# 4x4-soundboard.net
KiCad netlist of a schematic drawn in EAGLE
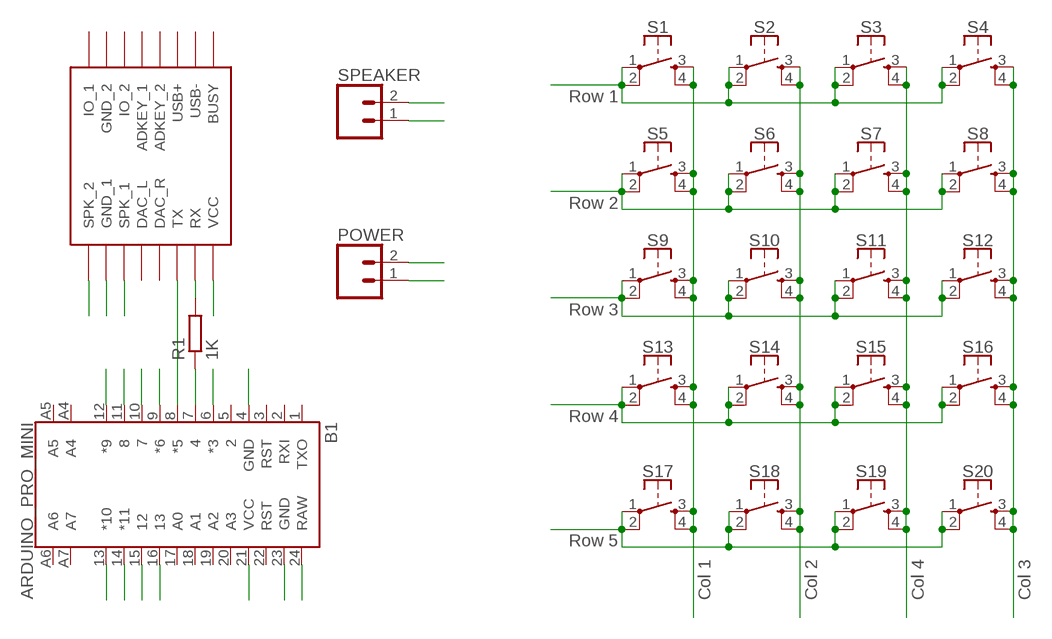
[diagram p0: schematic, sheet 1]

(export (version "E")
  (design (tool "Eeschema 10.0.6"))
  (components
    (comp (ref "B1")
      (value "ARDUINO_PRO_MINI")
      (footprint "eagle-import:ARDUINO_PRO_MINI")
      (libsource (lib "eagle-import") (part "ARDUINO_PRO_MINI"))
    )
    (comp (ref "POWER")
      (value "CONN_02")
      (footprint "eagle-import:1X02")
      (libsource (lib "eagle-import") (part "CONN_02"))
    )
    (comp (ref "R1")
      (value "1K")
      (footprint "eagle-import:0207_10")
      (libsource (lib "eagle-import") (part "R-EU_0207/10"))
    )
    (comp (ref "S1")
      (value "MOMENTARY-SWITCH-SPST-2-SMD-5.2MM")
      (footprint "eagle-import:TACTILE_SWITCH_SMD_5.2MM")
      (libsource (lib "eagle-import") (part "MOMENTARY-SWITCH-SPST-2-SMD-5.2MM"))
    )
    (comp (ref "S2")
      (value "MOMENTARY-SWITCH-SPST-2-SMD-5.2MM")
      (footprint "eagle-import:TACTILE_SWITCH_SMD_5.2MM")
      (libsource (lib "eagle-import") (part "MOMENTARY-SWITCH-SPST-2-SMD-5.2MM"))
    )
    (comp (ref "S3")
      (value "MOMENTARY-SWITCH-SPST-2-SMD-5.2MM")
      (footprint "eagle-import:TACTILE_SWITCH_SMD_5.2MM")
      (libsource (lib "eagle-import") (part "MOMENTARY-SWITCH-SPST-2-SMD-5.2MM"))
    )
    (comp (ref "S4")
      (value "MOMENTARY-SWITCH-SPST-2-SMD-5.2MM")
      (footprint "eagle-import:TACTILE_SWITCH_SMD_5.2MM")
      (libsource (lib "eagle-import") (part "MOMENTARY-SWITCH-SPST-2-SMD-5.2MM"))
    )
    (comp (ref "S5")
      (value "MOMENTARY-SWITCH-SPST-2-SMD-5.2MM")
      (footprint "eagle-import:TACTILE_SWITCH_SMD_5.2MM")
      (libsource (lib "eagle-import") (part "MOMENTARY-SWITCH-SPST-2-SMD-5.2MM"))
    )
    (comp (ref "S6")
      (value "MOMENTARY-SWITCH-SPST-2-SMD-5.2MM")
      (footprint "eagle-import:TACTILE_SWITCH_SMD_5.2MM")
      (libsource (lib "eagle-import") (part "MOMENTARY-SWITCH-SPST-2-SMD-5.2MM"))
    )
    (comp (ref "S7")
      (value "MOMENTARY-SWITCH-SPST-2-SMD-5.2MM")
      (footprint "eagle-import:TACTILE_SWITCH_SMD_5.2MM")
      (libsource (lib "eagle-import") (part "MOMENTARY-SWITCH-SPST-2-SMD-5.2MM"))
    )
    (comp (ref "S8")
      (value "MOMENTARY-SWITCH-SPST-2-SMD-5.2MM")
      (footprint "eagle-import:TACTILE_SWITCH_SMD_5.2MM")
      (libsource (lib "eagle-import") (part "MOMENTARY-SWITCH-SPST-2-SMD-5.2MM"))
    )
    (comp (ref "S9")
      (value "MOMENTARY-SWITCH-SPST-2-SMD-5.2MM")
      (footprint "eagle-import:TACTILE_SWITCH_SMD_5.2MM")
      (libsource (lib "eagle-import") (part "MOMENTARY-SWITCH-SPST-2-SMD-5.2MM"))
    )
    (comp (ref "S10")
      (value "MOMENTARY-SWITCH-SPST-2-SMD-5.2MM")
      (footprint "eagle-import:TACTILE_SWITCH_SMD_5.2MM")
      (libsource (lib "eagle-import") (part "MOMENTARY-SWITCH-SPST-2-SMD-5.2MM"))
    )
    (comp (ref "S11")
      (value "MOMENTARY-SWITCH-SPST-2-SMD-5.2MM")
      (footprint "eagle-import:TACTILE_SWITCH_SMD_5.2MM")
      (libsource (lib "eagle-import") (part "MOMENTARY-SWITCH-SPST-2-SMD-5.2MM"))
    )
    (comp (ref "S12")
      (value "MOMENTARY-SWITCH-SPST-2-SMD-5.2MM")
      (footprint "eagle-import:TACTILE_SWITCH_SMD_5.2MM")
      (libsource (lib "eagle-import") (part "MOMENTARY-SWITCH-SPST-2-SMD-5.2MM"))
    )
    (comp (ref "S13")
      (value "MOMENTARY-SWITCH-SPST-2-SMD-5.2MM")
      (footprint "eagle-import:TACTILE_SWITCH_SMD_5.2MM")
      (libsource (lib "eagle-import") (part "MOMENTARY-SWITCH-SPST-2-SMD-5.2MM"))
    )
    (comp (ref "S14")
      (value "MOMENTARY-SWITCH-SPST-2-SMD-5.2MM")
      (footprint "eagle-import:TACTILE_SWITCH_SMD_5.2MM")
      (libsource (lib "eagle-import") (part "MOMENTARY-SWITCH-SPST-2-SMD-5.2MM"))
    )
    (comp (ref "S15")
      (value "MOMENTARY-SWITCH-SPST-2-SMD-5.2MM")
      (footprint "eagle-import:TACTILE_SWITCH_SMD_5.2MM")
      (libsource (lib "eagle-import") (part "MOMENTARY-SWITCH-SPST-2-SMD-5.2MM"))
    )
    (comp (ref "S16")
      (value "MOMENTARY-SWITCH-SPST-2-SMD-5.2MM")
      (footprint "eagle-import:TACTILE_SWITCH_SMD_5.2MM")
      (libsource (lib "eagle-import") (part "MOMENTARY-SWITCH-SPST-2-SMD-5.2MM"))
    )
    (comp (ref "S17")
      (value "MOMENTARY-SWITCH-SPST-2-SMD-5.2MM")
      (footprint "eagle-import:TACTILE_SWITCH_SMD_5.2MM")
      (libsource (lib "eagle-import") (part "MOMENTARY-SWITCH-SPST-2-SMD-5.2MM"))
    )
    (comp (ref "S18")
      (value "MOMENTARY-SWITCH-SPST-2-SMD-5.2MM")
      (footprint "eagle-import:TACTILE_SWITCH_SMD_5.2MM")
      (libsource (lib "eagle-import") (part "MOMENTARY-SWITCH-SPST-2-SMD-5.2MM"))
    )
    (comp (ref "S19")
      (value "MOMENTARY-SWITCH-SPST-2-SMD-5.2MM")
      (footprint "eagle-import:TACTILE_SWITCH_SMD_5.2MM")
      (libsource (lib "eagle-import") (part "MOMENTARY-SWITCH-SPST-2-SMD-5.2MM"))
    )
    (comp (ref "S20")
      (value "MOMENTARY-SWITCH-SPST-2-SMD-5.2MM")
      (footprint "eagle-import:TACTILE_SWITCH_SMD_5.2MM")
      (libsource (lib "eagle-import") (part "MOMENTARY-SWITCH-SPST-2-SMD-5.2MM"))
    )
    (comp (ref "SPEAKER")
      (value "CONN_02")
      (footprint "eagle-import:1X02")
      (libsource (lib "eagle-import") (part "CONN_02"))
    )
    (comp (ref "U$1")
      (value "DFPLAYER")
      (footprint "eagle-import:DFPLAYER")
      (libsource (lib "eagle-import") (part "DFPLAYER"))
    )
  )
  (nets
    (net (code "1") (name "/5V") (class "Default")
      (node (ref "B1") (pin "21") (pinfunction "VCC_21") (pintype "power_in"))
      (node (ref "U$1") (pin "VCC") (pinfunction "VCC_VCC") (pintype "bidirectional"))
    )
    (net (code "2") (name "/COL1") (class "Default")
      (node (ref "B1") (pin "13") (pinfunction "*10_13") (pintype "bidirectional"))
      (node (ref "S1") (pin "3") (pinfunction "3_3") (pintype "passive"))
      (node (ref "S1") (pin "4") (pinfunction "4_4") (pintype "passive"))
      (node (ref "S13") (pin "3") (pinfunction "3_3") (pintype "passive"))
      (node (ref "S13") (pin "4") (pinfunction "4_4") (pintype "passive"))
      (node (ref "S17") (pin "3") (pinfunction "3_3") (pintype "passive"))
      (node (ref "S17") (pin "4") (pinfunction "4_4") (pintype "passive"))
      (node (ref "S5") (pin "3") (pinfunction "3_3") (pintype "passive"))
      (node (ref "S5") (pin "4") (pinfunction "4_4") (pintype "passive"))
      (node (ref "S9") (pin "3") (pinfunction "3_3") (pintype "passive"))
      (node (ref "S9") (pin "4") (pinfunction "4_4") (pintype "passive"))
    )
    (net (code "3") (name "/COL2") (class "Default")
      (node (ref "B1") (pin "14") (pinfunction "*11_14") (pintype "bidirectional"))
      (node (ref "S10") (pin "3") (pinfunction "3_3") (pintype "passive"))
      (node (ref "S10") (pin "4") (pinfunction "4_4") (pintype "passive"))
      (node (ref "S14") (pin "3") (pinfunction "3_3") (pintype "passive"))
      (node (ref "S14") (pin "4") (pinfunction "4_4") (pintype "passive"))
      (node (ref "S18") (pin "3") (pinfunction "3_3") (pintype "passive"))
      (node (ref "S18") (pin "4") (pinfunction "4_4") (pintype "passive"))
      (node (ref "S2") (pin "3") (pinfunction "3_3") (pintype "passive"))
      (node (ref "S2") (pin "4") (pinfunction "4_4") (pintype "passive"))
      (node (ref "S6") (pin "3") (pinfunction "3_3") (pintype "passive"))
      (node (ref "S6") (pin "4") (pinfunction "4_4") (pintype "passive"))
    )
    (net (code "4") (name "/COL3") (class "Default")
      (node (ref "B1") (pin "15") (pinfunction "12_15") (pintype "bidirectional"))
      (node (ref "S11") (pin "3") (pinfunction "3_3") (pintype "passive"))
      (node (ref "S11") (pin "4") (pinfunction "4_4") (pintype "passive"))
      (node (ref "S15") (pin "3") (pinfunction "3_3") (pintype "passive"))
      (node (ref "S15") (pin "4") (pinfunction "4_4") (pintype "passive"))
      (node (ref "S19") (pin "3") (pinfunction "3_3") (pintype "passive"))
      (node (ref "S19") (pin "4") (pinfunction "4_4") (pintype "passive"))
      (node (ref "S3") (pin "3") (pinfunction "3_3") (pintype "passive"))
      (node (ref "S3") (pin "4") (pinfunction "4_4") (pintype "passive"))
      (node (ref "S7") (pin "3") (pinfunction "3_3") (pintype "passive"))
      (node (ref "S7") (pin "4") (pinfunction "4_4") (pintype "passive"))
    )
    (net (code "5") (name "/COL4") (class "Default")
      (node (ref "B1") (pin "16") (pinfunction "13_16") (pintype "bidirectional"))
      (node (ref "S12") (pin "3") (pinfunction "3_3") (pintype "passive"))
      (node (ref "S12") (pin "4") (pinfunction "4_4") (pintype "passive"))
      (node (ref "S16") (pin "3") (pinfunction "3_3") (pintype "passive"))
      (node (ref "S16") (pin "4") (pinfunction "4_4") (pintype "passive"))
      (node (ref "S20") (pin "3") (pinfunction "3_3") (pintype "passive"))
      (node (ref "S20") (pin "4") (pinfunction "4_4") (pintype "passive"))
      (node (ref "S4") (pin "3") (pinfunction "3_3") (pintype "passive"))
      (node (ref "S4") (pin "4") (pinfunction "4_4") (pintype "passive"))
      (node (ref "S8") (pin "3") (pinfunction "3_3") (pintype "passive"))
      (node (ref "S8") (pin "4") (pinfunction "4_4") (pintype "passive"))
    )
    (net (code "6") (name "/GND") (class "Default")
      (node (ref "B1") (pin "23") (pinfunction "GND_23") (pintype "power_in"))
      (node (ref "B1") (pin "4") (pinfunction "GND_4") (pintype "power_in"))
      (node (ref "POWER") (pin "2") (pinfunction "2_2") (pintype "passive"))
      (node (ref "U$1") (pin "GND_1") (pinfunction "GND_1_GND_1") (pintype "bidirectional"))
    )
    (net (code "7") (name "/ROW2") (class "Default")
      (node (ref "B1") (pin "9") (pinfunction "*6_9") (pintype "bidirectional"))
      (node (ref "S5") (pin "1") (pinfunction "1_1") (pintype "passive"))
      (node (ref "S5") (pin "2") (pinfunction "2_2") (pintype "passive"))
      (node (ref "S6") (pin "1") (pinfunction "1_1") (pintype "passive"))
      (node (ref "S6") (pin "2") (pinfunction "2_2") (pintype "passive"))
      (node (ref "S7") (pin "1") (pinfunction "1_1") (pintype "passive"))
      (node (ref "S7") (pin "2") (pinfunction "2_2") (pintype "passive"))
      (node (ref "S8") (pin "1") (pinfunction "1_1") (pintype "passive"))
      (node (ref "S8") (pin "2") (pinfunction "2_2") (pintype "passive"))
    )
    (net (code "8") (name "/ROW3") (class "Default")
      (node (ref "B1") (pin "10") (pinfunction "7_10") (pintype "bidirectional"))
      (node (ref "S10") (pin "1") (pinfunction "1_1") (pintype "passive"))
      (node (ref "S10") (pin "2") (pinfunction "2_2") (pintype "passive"))
      (node (ref "S11") (pin "1") (pinfunction "1_1") (pintype "passive"))
      (node (ref "S11") (pin "2") (pinfunction "2_2") (pintype "passive"))
      (node (ref "S12") (pin "1") (pinfunction "1_1") (pintype "passive"))
      (node (ref "S12") (pin "2") (pinfunction "2_2") (pintype "passive"))
      (node (ref "S9") (pin "1") (pinfunction "1_1") (pintype "passive"))
      (node (ref "S9") (pin "2") (pinfunction "2_2") (pintype "passive"))
    )
    (net (code "9") (name "/ROW4") (class "Default")
      (node (ref "B1") (pin "11") (pinfunction "8_11") (pintype "bidirectional"))
      (node (ref "S13") (pin "1") (pinfunction "1_1") (pintype "passive"))
      (node (ref "S13") (pin "2") (pinfunction "2_2") (pintype "passive"))
      (node (ref "S14") (pin "1") (pinfunction "1_1") (pintype "passive"))
      (node (ref "S14") (pin "2") (pinfunction "2_2") (pintype "passive"))
      (node (ref "S15") (pin "1") (pinfunction "1_1") (pintype "passive"))
      (node (ref "S15") (pin "2") (pinfunction "2_2") (pintype "passive"))
      (node (ref "S16") (pin "1") (pinfunction "1_1") (pintype "passive"))
      (node (ref "S16") (pin "2") (pinfunction "2_2") (pintype "passive"))
    )
    (net (code "10") (name "/ROW5") (class "Default")
      (node (ref "B1") (pin "12") (pinfunction "*9_12") (pintype "bidirectional"))
      (node (ref "S17") (pin "1") (pinfunction "1_1") (pintype "passive"))
      (node (ref "S17") (pin "2") (pinfunction "2_2") (pintype "passive"))
      (node (ref "S18") (pin "1") (pinfunction "1_1") (pintype "passive"))
      (node (ref "S18") (pin "2") (pinfunction "2_2") (pintype "passive"))
      (node (ref "S19") (pin "1") (pinfunction "1_1") (pintype "passive"))
      (node (ref "S19") (pin "2") (pinfunction "2_2") (pintype "passive"))
      (node (ref "S20") (pin "1") (pinfunction "1_1") (pintype "passive"))
      (node (ref "S20") (pin "2") (pinfunction "2_2") (pintype "passive"))
    )
    (net (code "11") (name "/SPK+") (class "Default")
      (node (ref "SPEAKER") (pin "1") (pinfunction "1_1") (pintype "passive"))
      (node (ref "U$1") (pin "SPK1") (pinfunction "SPK_1_SPK1") (pintype "bidirectional"))
    )
    (net (code "12") (name "/SPK-") (class "Default")
      (node (ref "SPEAKER") (pin "2") (pinfunction "2_2") (pintype "passive"))
      (node (ref "U$1") (pin "SPK2") (pinfunction "SPK_2_SPK2") (pintype "bidirectional"))
    )
    (net (code "13") (name "/SRX") (class "Default")
      (node (ref "B1") (pin "6") (pinfunction "*3_6") (pintype "bidirectional"))
      (node (ref "B1") (pin "8") (pinfunction "*5_8") (pintype "bidirectional"))
      (node (ref "U$1") (pin "TX") (pinfunction "TX_TX") (pintype "bidirectional"))
    )
    (net (code "14") (name "/VIN") (class "Default")
      (node (ref "B1") (pin "24") (pinfunction "RAW_24") (pintype "power_in"))
      (node (ref "POWER") (pin "1") (pinfunction "1_1") (pintype "passive"))
    )
    (net (code "15") (name "Net-(B1-4)") (class "Default")
      (node (ref "B1") (pin "7") (pinfunction "4_7") (pintype "bidirectional"))
      (node (ref "R1") (pin "1") (pinfunction "1_1") (pintype "passive"))
    )
    (net (code "16") (name "Net-(R1-Pad2)") (class "Default")
      (node (ref "R1") (pin "2") (pinfunction "2_2") (pintype "passive"))
      (node (ref "U$1") (pin "RX") (pinfunction "RX_RX") (pintype "bidirectional"))
    )
    (net (code "17") (name "Net-(S1-Pad1)") (class "Default")
      (node (ref "S1") (pin "1") (pinfunction "1_1") (pintype "passive"))
      (node (ref "S1") (pin "2") (pinfunction "2_2") (pintype "passive"))
      (node (ref "S2") (pin "1") (pinfunction "1_1") (pintype "passive"))
      (node (ref "S2") (pin "2") (pinfunction "2_2") (pintype "passive"))
      (node (ref "S3") (pin "1") (pinfunction "1_1") (pintype "passive"))
      (node (ref "S3") (pin "2") (pinfunction "2_2") (pintype "passive"))
      (node (ref "S4") (pin "1") (pinfunction "1_1") (pintype "passive"))
      (node (ref "S4") (pin "2") (pinfunction "2_2") (pintype "passive"))
    )
    (net (code "18") (name "unconnected-(B1-2-Pad5)") (class "Default")
      (node (ref "B1") (pin "5") (pinfunction "2_5") (pintype "bidirectional"))
    )
    (net (code "19") (name "unconnected-(B1-A0-Pad17)") (class "Default")
      (node (ref "B1") (pin "17") (pinfunction "A0_17") (pintype "bidirectional"))
    )
    (net (code "20") (name "unconnected-(B1-A1-Pad18)") (class "Default")
      (node (ref "B1") (pin "18") (pinfunction "A1_18") (pintype "bidirectional"))
    )
    (net (code "21") (name "unconnected-(B1-A2-Pad19)") (class "Default")
      (node (ref "B1") (pin "19") (pinfunction "A2_19") (pintype "bidirectional"))
    )
    (net (code "22") (name "unconnected-(B1-A3-Pad20)") (class "Default")
      (node (ref "B1") (pin "20") (pinfunction "A3_20") (pintype "bidirectional"))
    )
    (net (code "23") (name "unconnected-(B1-PadA4)") (class "Default")
      (node (ref "B1") (pin "A4") (pinfunction "A4_A4") (pintype "bidirectional"))
    )
    (net (code "24") (name "unconnected-(B1-PadA5)") (class "Default")
      (node (ref "B1") (pin "A5") (pinfunction "A5_A5") (pintype "bidirectional"))
    )
    (net (code "25") (name "unconnected-(B1-PadA6)") (class "Default")
      (node (ref "B1") (pin "A6") (pinfunction "A6_A6") (pintype "bidirectional"))
    )
    (net (code "26") (name "unconnected-(B1-PadA7)") (class "Default")
      (node (ref "B1") (pin "A7") (pinfunction "A7_A7") (pintype "bidirectional"))
    )
    (net (code "27") (name "unconnected-(B1-RST-Pad3)") (class "Default")
      (node (ref "B1") (pin "3") (pinfunction "RST_3") (pintype "bidirectional"))
    )
    (net (code "28") (name "unconnected-(B1-RST-Pad22)") (class "Default")
      (node (ref "B1") (pin "22") (pinfunction "RST_22") (pintype "bidirectional"))
    )
    (net (code "29") (name "unconnected-(B1-RXI-Pad2)") (class "Default")
      (node (ref "B1") (pin "2") (pinfunction "RXI_2") (pintype "bidirectional"))
    )
    (net (code "30") (name "unconnected-(B1-TXO-Pad1)") (class "Default")
      (node (ref "B1") (pin "1") (pinfunction "TXO_1") (pintype "bidirectional"))
    )
    (net (code "31") (name "unconnected-(U$1-ADKEY_1-PadADKEY1)") (class "Default")
      (node (ref "U$1") (pin "ADKEY1") (pinfunction "ADKEY_1_ADKEY1") (pintype "bidirectional"))
    )
    (net (code "32") (name "unconnected-(U$1-ADKEY_2-PadADKEY2)") (class "Default")
      (node (ref "U$1") (pin "ADKEY2") (pinfunction "ADKEY_2_ADKEY2") (pintype "bidirectional"))
    )
    (net (code "33") (name "unconnected-(U$1-IO_1-PadIO1)") (class "Default")
      (node (ref "U$1") (pin "IO1") (pinfunction "IO_1_IO1") (pintype "bidirectional"))
    )
    (net (code "34") (name "unconnected-(U$1-IO_2-PadIO2)") (class "Default")
      (node (ref "U$1") (pin "IO2") (pinfunction "IO_2_IO2") (pintype "bidirectional"))
    )
    (net (code "35") (name "unconnected-(U$1-PadBUSY)") (class "Default")
      (node (ref "U$1") (pin "BUSY") (pinfunction "BUSY_BUSY") (pintype "bidirectional"))
    )
    (net (code "36") (name "unconnected-(U$1-PadDAC_L)") (class "Default")
      (node (ref "U$1") (pin "DAC_L") (pinfunction "DAC_L_DAC_L") (pintype "bidirectional"))
    )
    (net (code "37") (name "unconnected-(U$1-PadDAC_R)") (class "Default")
      (node (ref "U$1") (pin "DAC_R") (pinfunction "DAC_R_DAC_R") (pintype "bidirectional"))
    )
    (net (code "38") (name "unconnected-(U$1-PadGND_2)") (class "Default")
      (node (ref "U$1") (pin "GND_2") (pinfunction "GND_2_GND_2") (pintype "bidirectional"))
    )
    (net (code "39") (name "unconnected-(U$1-PadUSB+)") (class "Default")
      (node (ref "U$1") (pin "USB+") (pinfunction "USB+_USB+") (pintype "bidirectional"))
    )
    (net (code "40") (name "unconnected-(U$1-PadUSB-)") (class "Default")
      (node (ref "U$1") (pin "USB-") (pinfunction "USB-_USB-") (pintype "bidirectional"))
    )
  )
)
